# Nu_Module.net
KiCad netlist of a schematic drawn in EAGLE
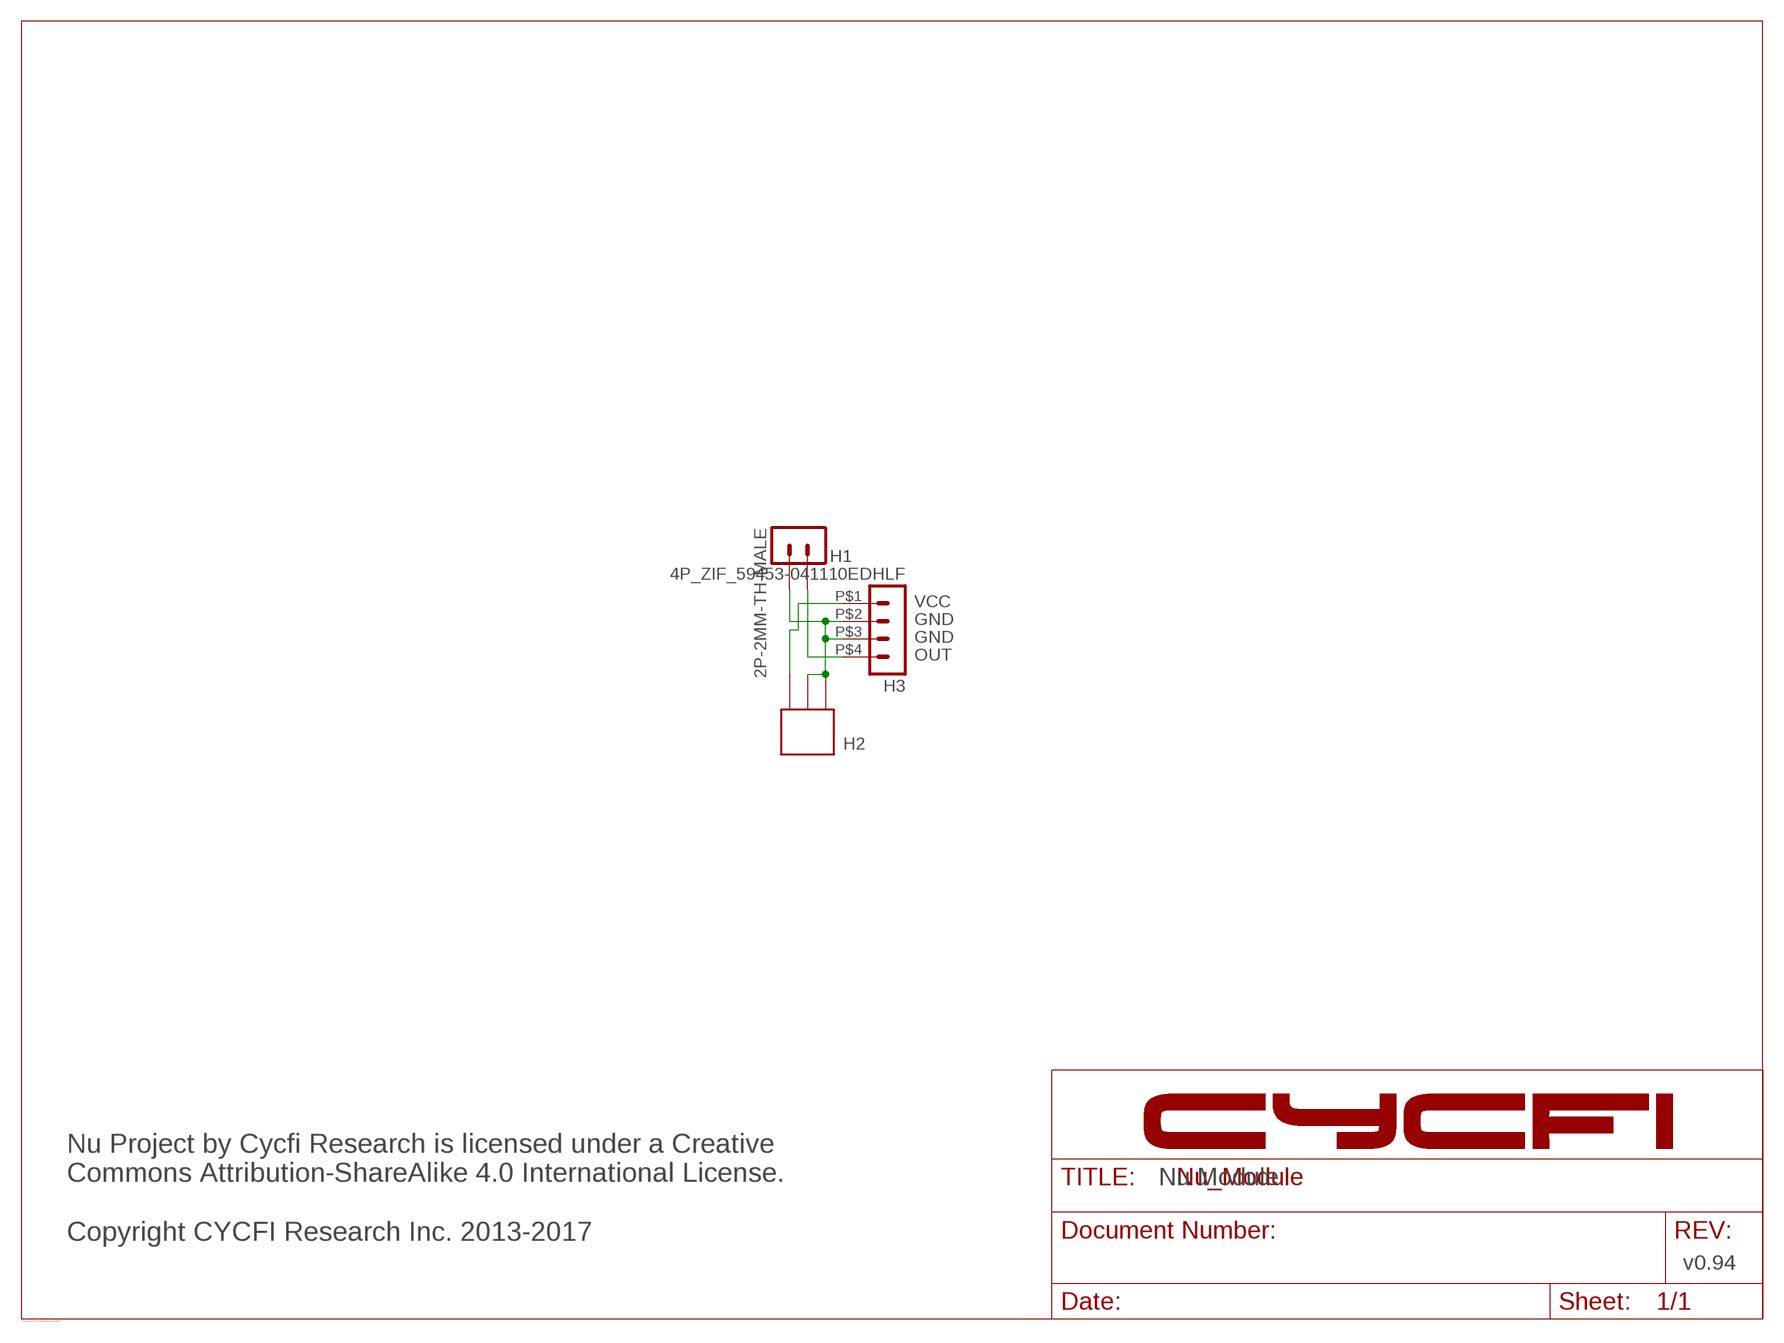
[diagram p0: schematic, sheet 1]

(export (version "E")
  (design (tool "Eeschema 10.0.6"))
  (components
    (comp (ref "H1")
      (value "2P-2MM-TH-MALE")
      (footprint "eagle-import:2P-2MM-TH")
      (libsource (lib "eagle-import") (part "2P-2MM-TH-MALE"))
    )
    (comp (ref "H2")
      (value "951102-8622-AR")
      (footprint "eagle-import:3P-TH-2MM")
      (libsource (lib "eagle-import") (part "951102-8622-AR"))
    )
    (comp (ref "H3")
      (value "4P_ZIF_59453-041110EDHLF")
      (footprint "eagle-import:4P_ZIF_59453-041110EDHLF")
      (libsource (lib "eagle-import") (part "4P_ZIF_59453-041110EDHLF"))
    )
  )
  (nets
    (net (code "1") (name "Net-(H1-1)") (class "Default")
      (node (ref "H1") (pin "P$1") (pinfunction "1_P$1") (pintype "passive"))
      (node (ref "H2") (pin "P$1") (pinfunction "P$1_P$1") (pintype "bidirectional"))
      (node (ref "H2") (pin "P$2") (pinfunction "P$2_P$2") (pintype "bidirectional"))
      (node (ref "H3") (pin "P$2") (pinfunction "2_P$2") (pintype "passive"))
      (node (ref "H3") (pin "P$3") (pinfunction "3_P$3") (pintype "passive"))
    )
    (net (code "2") (name "Net-(H1-2)") (class "Default")
      (node (ref "H1") (pin "P$2") (pinfunction "2_P$2") (pintype "passive"))
      (node (ref "H3") (pin "P$4") (pinfunction "4_P$4") (pintype "passive"))
    )
    (net (code "3") (name "Net-(H3-1)") (class "Default")
      (node (ref "H2") (pin "P$3") (pinfunction "P$3_P$3") (pintype "bidirectional"))
      (node (ref "H3") (pin "P$1") (pinfunction "1_P$1") (pintype "passive"))
    )
  )
)
